# RSheet4.net
KiCad netlist of a schematic drawn in Altium Designer
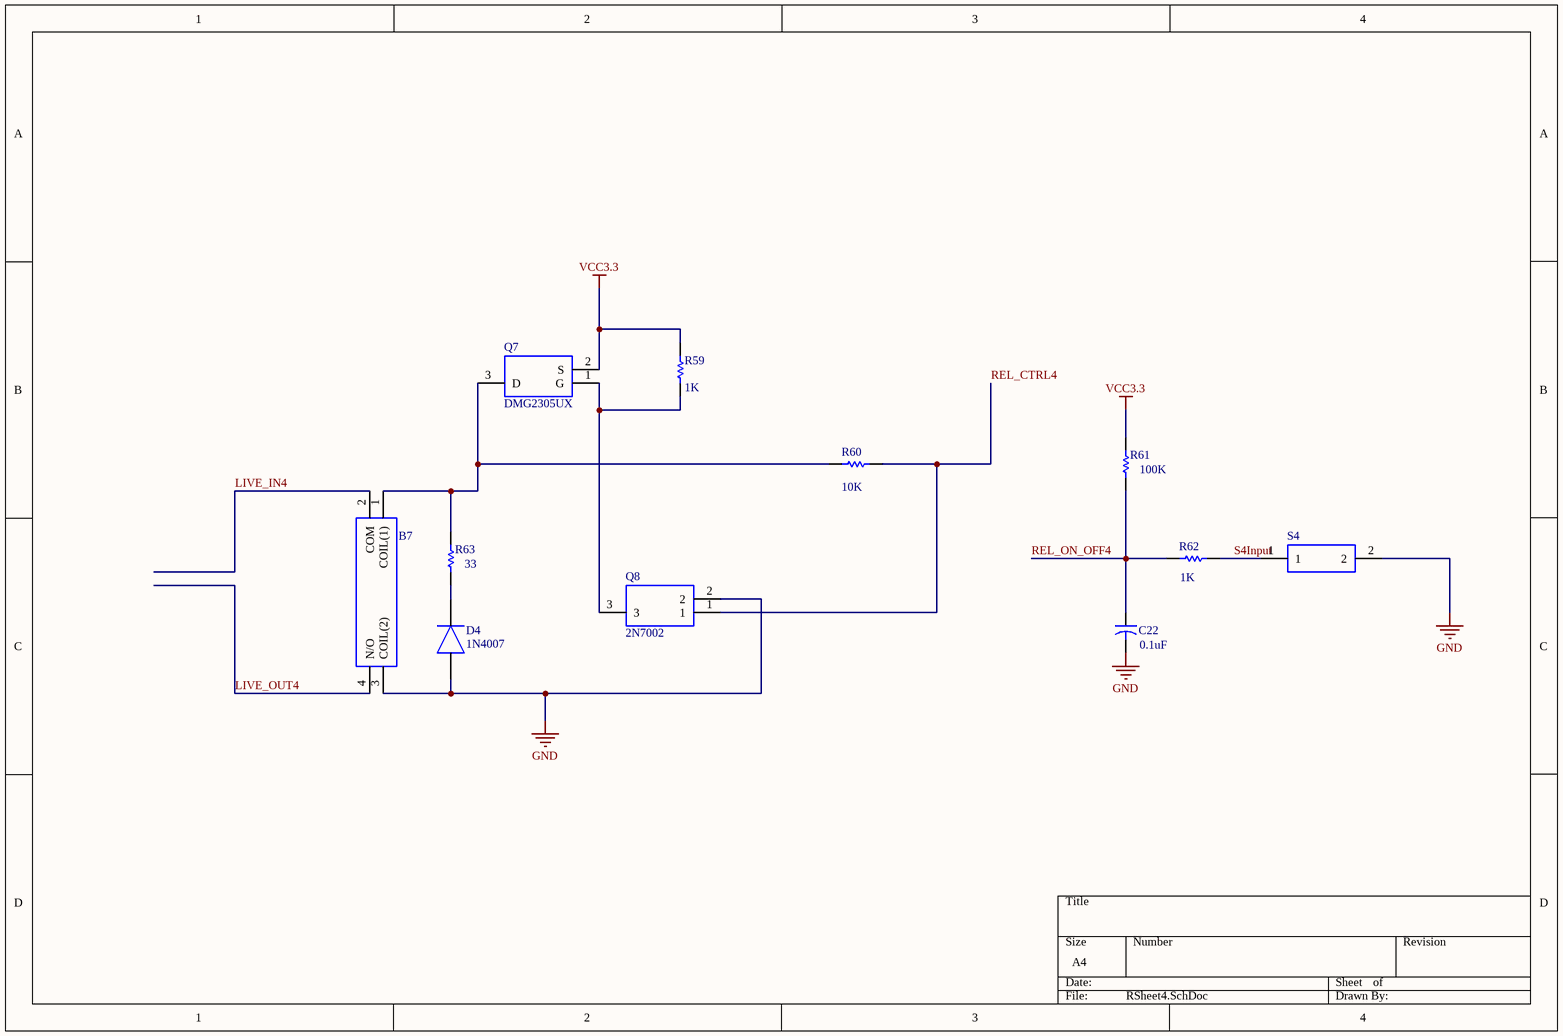
[diagram p0: RSheet4.SchDoc]

(export (version "E")
  (design (tool "Eeschema 10.0.6"))
  (components
    (comp (ref "B7")
      (value "HF3FA_005-HTF")
      (footprint "HF3FA005HTF:HF3FA005HTF")
      (description "Subminiature high power relay. 10A 5V.")
      (fields (field (name "MANUFACTURER_PART_NUMBER") "HF3FA/005-HTF"))
      (libsource (lib "HF3FA_005-HTF") (part "HF3FA_005-HTF"))
    )
    (comp (ref "C22")
      (value "0.1uF")
      (footprint "RESC0603X26N:RESC0603X26N")
      (description "Capacitor")
      (fields (field (name "Comment") "Cap2") (field (name "PUBLISHER") "Altium Limited"))
      (libsource (lib "Miscellaneous Devices") (part "Cap2"))
    )
    (comp (ref "D4")
      (value "1N4007")
      (footprint "DIOAD1408W86L464D236:DIOAD1408W86L464D236")
      (description "Diode Standard 1A 1000V 1Vf DO41 Diodes Inc 1N4007-T, Switching Diode, 1000V 1A, 2-Pin DO-41")
      (fields (field (name "RS PART NUMBER") "7384724P") (field (name "MANUFACTURER_PART_NUMBER") "1N4007-T"))
      (libsource (lib "1N4007-T") (part "1N4007-T"))
    )
    (comp (ref "Q7")
      (value "DMG2305UX")
      (footprint "SOT96P240X100-3N:SOT96P240X100-3N")
      (fields
        (field (name "RS PART NUMBER") "1219640")
        (field (name "MANUFACTURER_PART_NUMBER") "DMG2305UX-7")
      )
      (libsource (lib "DMG2305UX-7") (part "DMG2305UX-7"))
    )
    (comp (ref "Q8")
      (value "2N7002")
      (footprint "SOT95P230X110-3N:SOT95P230X110-3N")
      (fields
        (field (name "RS PART NUMBER") "1125526")
        (field (name "MANUFACTURER_PART_NUMBER") "2N7002,215")
      )
      (libsource (lib "2N7002_215") (part "2N7002_215"))
    )
    (comp (ref "R59")
      (value "1K")
      (footprint "AXIAL-0.3")
      (description "Resistor")
      (fields (field (name "Comment") "Res1") (field (name "PUBLISHER") "Altium Limited"))
      (libsource (lib "Miscellaneous Devices") (part "Res1"))
    )
    (comp (ref "R60")
      (value "10K")
      (footprint "AXIAL-0.3")
      (description "Resistor")
      (fields (field (name "Comment") "Res1") (field (name "PUBLISHER") "Altium Limited"))
      (libsource (lib "Miscellaneous Devices") (part "Res1"))
    )
    (comp (ref "R61")
      (value "100K")
      (footprint "RESC0603X26N:RESC0603X26N")
      (description "Resistor")
      (fields (field (name "Comment") "Res1") (field (name "PUBLISHER") "Altium Limited"))
      (libsource (lib "Miscellaneous Devices") (part "Res1"))
    )
    (comp (ref "R62")
      (value "1K")
      (footprint "RESC0603X26N:RESC0603X26N")
      (description "Resistor")
      (fields (field (name "Comment") "Res1") (field (name "PUBLISHER") "Altium Limited"))
      (libsource (lib "Miscellaneous Devices") (part "Res1"))
    )
    (comp (ref "R63")
      (value "33")
      (footprint "AXIAL-0.3")
      (description "Resistor")
      (fields (field (name "PUBLISHER") "Altium Limited"))
      (libsource (lib "Miscellaneous Devices") (part "Res1"))
    )
    (comp (ref "S4")
      (value "TL3330AF260QG")
      (footprint "SMD & J-Bend Tact Switch WS-TASV:434121043836")
      (description "Tactile Switches 50mA@12VDC 260g OF Silver contacts")
      (libsource (lib "TL3330AF260QG") (part "TL3330AF260QG"))
    )
  )
  (nets
    (net (code "1") (name "/LIVE_IN4") (class "Default")
      (node (ref "B7") (pin "2") (pinfunction "COM_2") (pintype "passive"))
    )
    (net (code "2") (name "/LIVE_OUT4") (class "Default")
      (node (ref "B7") (pin "4") (pinfunction "N/O_4") (pintype "passive"))
    )
    (net (code "3") (name "/REL_CTRL4") (class "Default")
      (node (ref "Q8") (pin "1") (pinfunction "1_1") (pintype "passive"))
      (node (ref "R60") (pin "2") (pinfunction "2_2") (pintype "passive"))
    )
    (net (code "4") (name "/REL_ON_OFF4") (class "Default")
      (node (ref "C22") (pin "1") (pinfunction "1_1") (pintype "passive"))
      (node (ref "R61") (pin "1") (pinfunction "1_1") (pintype "passive"))
      (node (ref "R62") (pin "1") (pinfunction "1_1") (pintype "passive"))
    )
    (net (code "5") (name "/S4Input") (class "Default")
      (node (ref "R62") (pin "2") (pinfunction "2_2") (pintype "passive"))
      (node (ref "S4") (pin "1") (pinfunction "1_1") (pintype "passive"))
    )
    (net (code "6") (name "GND") (class "Default")
      (node (ref "B7") (pin "3") (pinfunction "COIL(2)_3") (pintype "passive"))
      (node (ref "C22") (pin "2") (pinfunction "2_2") (pintype "passive"))
      (node (ref "D4") (pin "2") (pinfunction "A_2") (pintype "passive"))
      (node (ref "Q8") (pin "2") (pinfunction "2_2") (pintype "passive"))
      (node (ref "S4") (pin "2") (pinfunction "2_2") (pintype "passive"))
    )
    (net (code "7") (name "Net-(B7-COIL(1))") (class "Default")
      (node (ref "B7") (pin "1") (pinfunction "COIL(1)_1") (pintype "passive"))
      (node (ref "Q7") (pin "3") (pinfunction "D_3") (pintype "passive"))
      (node (ref "R60") (pin "1") (pinfunction "1_1") (pintype "passive"))
      (node (ref "R63") (pin "2") (pinfunction "2_2") (pintype "passive"))
    )
    (net (code "8") (name "Net-(D4-K)") (class "Default")
      (node (ref "D4") (pin "1") (pinfunction "K_1") (pintype "passive"))
      (node (ref "R63") (pin "1") (pinfunction "1_1") (pintype "passive"))
    )
    (net (code "9") (name "Net-(Q7-G)") (class "Default")
      (node (ref "Q7") (pin "1") (pinfunction "G_1") (pintype "passive"))
      (node (ref "Q8") (pin "3") (pinfunction "3_3") (pintype "passive"))
      (node (ref "R59") (pin "1") (pinfunction "1_1") (pintype "passive"))
    )
    (net (code "10") (name "VCC3.3") (class "Default")
      (node (ref "Q7") (pin "2") (pinfunction "S_2") (pintype "passive"))
      (node (ref "R59") (pin "2") (pinfunction "2_2") (pintype "passive"))
      (node (ref "R61") (pin "2") (pinfunction "2_2") (pintype "passive"))
    )
  )
)
